# InverterConnector.net
KiCad netlist of a schematic drawn in Altium Designer
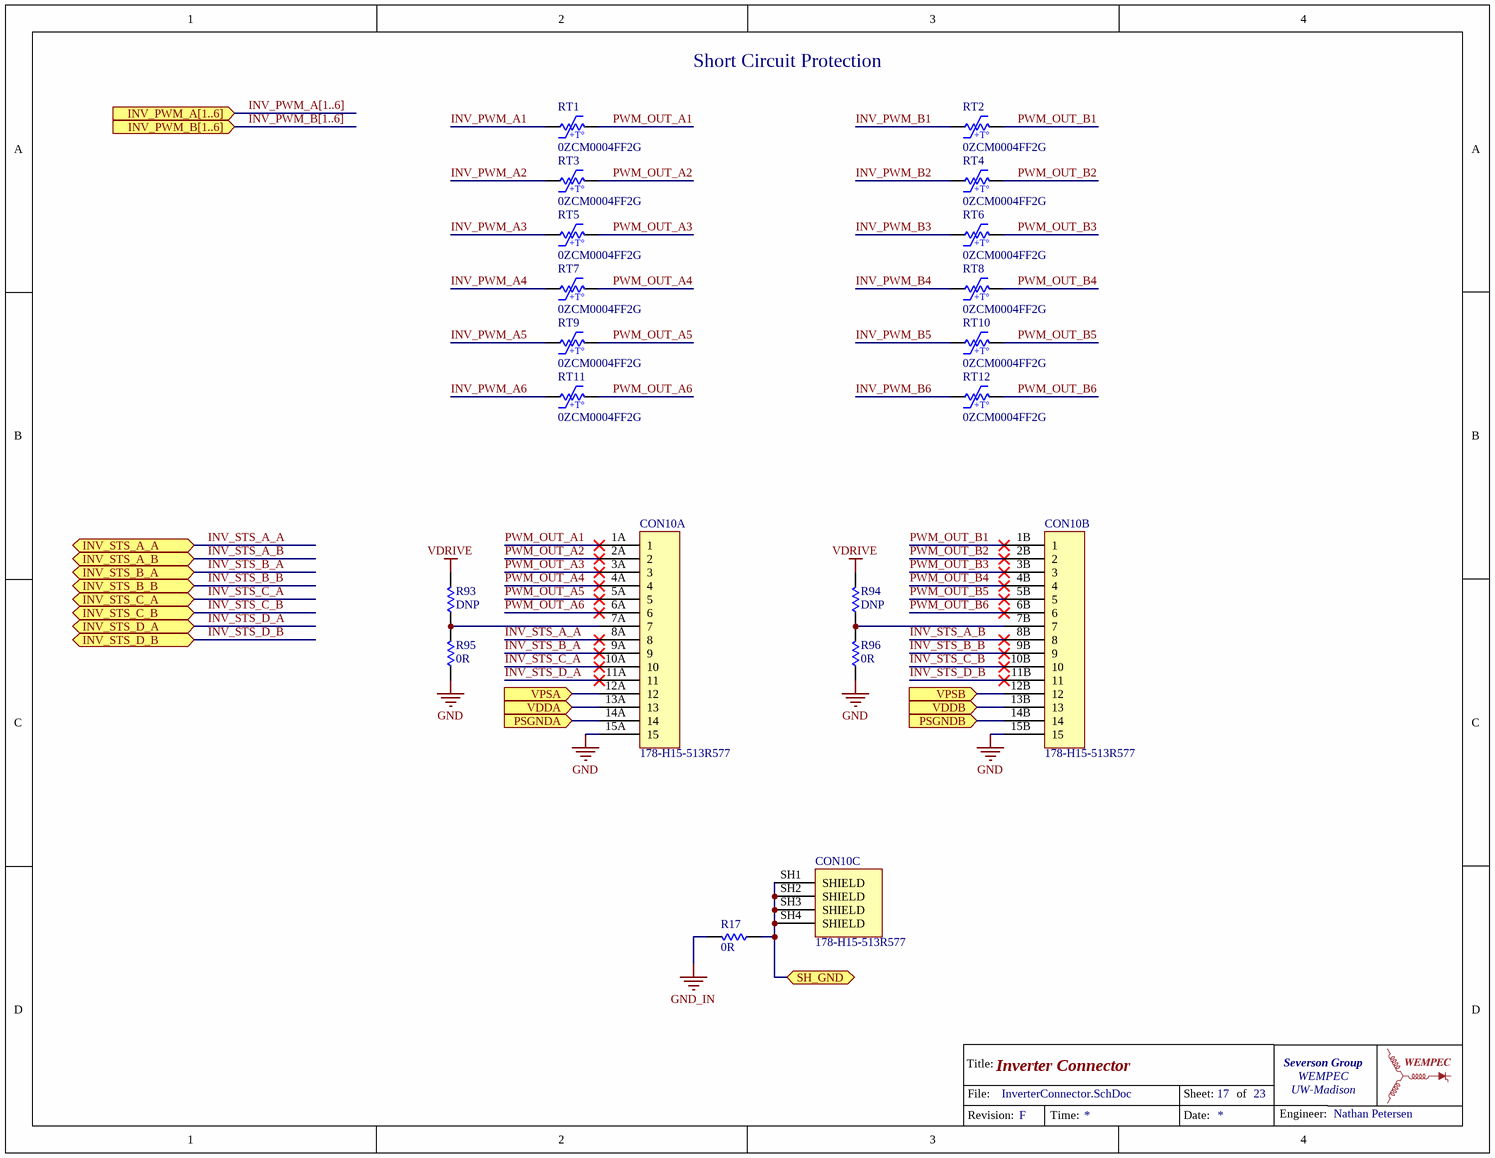
[diagram p0: InverterConnector.SchDoc]

(export (version "E")
  (design (tool "Eeschema 10.0.6"))
  (components
    (comp (ref "CON10")
      (value "178-H15-513R577")
      (footprint "178-H15-513R577")
      (description "CONN D-SUB PLUG 15POS R/A SLDR")
      (libsource (lib "AMDC") (part "178-H15-513R577"))
    )
    (comp (ref "R17")
      (value "0R")
      (footprint "1206-RES")
      (description "Resistor")
      (libsource (lib "AMDC") (part "Resistor"))
    )
    (comp (ref "R93")
      (value "DNP")
      (footprint "1206-RES")
      (description "Resistor")
      (libsource (lib "AMDC") (part "Resistor"))
    )
    (comp (ref "R94")
      (value "DNP")
      (footprint "1206-RES")
      (description "Resistor")
      (libsource (lib "AMDC") (part "Resistor"))
    )
    (comp (ref "R95")
      (value "0R")
      (footprint "1206-RES")
      (description "Resistor")
      (libsource (lib "AMDC") (part "Resistor"))
    )
    (comp (ref "R96")
      (value "0R")
      (footprint "1206-RES")
      (description "Resistor")
      (libsource (lib "AMDC") (part "Resistor"))
    )
    (comp (ref "RT1")
      (value "0ZCM0004FF2G")
      (footprint "PTCC1607X06N")
      (description "PTC RESET FUSE 24V 40MA 0603")
      (libsource (lib "AMDC") (part "0ZCM0004FF2G"))
    )
    (comp (ref "RT2")
      (value "0ZCM0004FF2G")
      (footprint "PTCC1607X06N")
      (description "PTC RESET FUSE 24V 40MA 0603")
      (libsource (lib "AMDC") (part "0ZCM0004FF2G"))
    )
    (comp (ref "RT3")
      (value "0ZCM0004FF2G")
      (footprint "PTCC1607X06N")
      (description "PTC RESET FUSE 24V 40MA 0603")
      (libsource (lib "AMDC") (part "0ZCM0004FF2G"))
    )
    (comp (ref "RT4")
      (value "0ZCM0004FF2G")
      (footprint "PTCC1607X06N")
      (description "PTC RESET FUSE 24V 40MA 0603")
      (libsource (lib "AMDC") (part "0ZCM0004FF2G"))
    )
    (comp (ref "RT5")
      (value "0ZCM0004FF2G")
      (footprint "PTCC1607X06N")
      (description "PTC RESET FUSE 24V 40MA 0603")
      (libsource (lib "AMDC") (part "0ZCM0004FF2G"))
    )
    (comp (ref "RT6")
      (value "0ZCM0004FF2G")
      (footprint "PTCC1607X06N")
      (description "PTC RESET FUSE 24V 40MA 0603")
      (libsource (lib "AMDC") (part "0ZCM0004FF2G"))
    )
    (comp (ref "RT7")
      (value "0ZCM0004FF2G")
      (footprint "PTCC1607X06N")
      (description "PTC RESET FUSE 24V 40MA 0603")
      (libsource (lib "AMDC") (part "0ZCM0004FF2G"))
    )
    (comp (ref "RT8")
      (value "0ZCM0004FF2G")
      (footprint "PTCC1607X06N")
      (description "PTC RESET FUSE 24V 40MA 0603")
      (libsource (lib "AMDC") (part "0ZCM0004FF2G"))
    )
    (comp (ref "RT9")
      (value "0ZCM0004FF2G")
      (footprint "PTCC1607X06N")
      (description "PTC RESET FUSE 24V 40MA 0603")
      (libsource (lib "AMDC") (part "0ZCM0004FF2G"))
    )
    (comp (ref "RT10")
      (value "0ZCM0004FF2G")
      (footprint "PTCC1607X06N")
      (description "PTC RESET FUSE 24V 40MA 0603")
      (libsource (lib "AMDC") (part "0ZCM0004FF2G"))
    )
    (comp (ref "RT11")
      (value "0ZCM0004FF2G")
      (footprint "PTCC1607X06N")
      (description "PTC RESET FUSE 24V 40MA 0603")
      (libsource (lib "AMDC") (part "0ZCM0004FF2G"))
    )
    (comp (ref "RT12")
      (value "0ZCM0004FF2G")
      (footprint "PTCC1607X06N")
      (description "PTC RESET FUSE 24V 40MA 0603")
      (libsource (lib "AMDC") (part "0ZCM0004FF2G"))
    )
  )
  (nets
    (net (code "1") (name "/INV_PWM_A1") (class "Default")
      (node (ref "RT1") (pin "1") (pinfunction "1_1") (pintype "passive"))
    )
    (net (code "2") (name "/INV_PWM_A2") (class "Default")
      (node (ref "RT3") (pin "1") (pinfunction "1_1") (pintype "passive"))
    )
    (net (code "3") (name "/INV_PWM_A3") (class "Default")
      (node (ref "RT5") (pin "1") (pinfunction "1_1") (pintype "passive"))
    )
    (net (code "4") (name "/INV_PWM_A4") (class "Default")
      (node (ref "RT7") (pin "1") (pinfunction "1_1") (pintype "passive"))
    )
    (net (code "5") (name "/INV_PWM_A5") (class "Default")
      (node (ref "RT9") (pin "1") (pinfunction "1_1") (pintype "passive"))
    )
    (net (code "6") (name "/INV_PWM_A6") (class "Default")
      (node (ref "RT11") (pin "1") (pinfunction "1_1") (pintype "passive"))
    )
    (net (code "8") (name "/INV_PWM_B1") (class "Default")
      (node (ref "RT2") (pin "1") (pinfunction "1_1") (pintype "passive"))
    )
    (net (code "9") (name "/INV_PWM_B2") (class "Default")
      (node (ref "RT4") (pin "1") (pinfunction "1_1") (pintype "passive"))
    )
    (net (code "10") (name "/INV_PWM_B3") (class "Default")
      (node (ref "RT6") (pin "1") (pinfunction "1_1") (pintype "passive"))
    )
    (net (code "11") (name "/INV_PWM_B4") (class "Default")
      (node (ref "RT8") (pin "1") (pinfunction "1_1") (pintype "passive"))
    )
    (net (code "12") (name "/INV_PWM_B5") (class "Default")
      (node (ref "RT10") (pin "1") (pinfunction "1_1") (pintype "passive"))
    )
    (net (code "13") (name "/INV_PWM_B6") (class "Default")
      (node (ref "RT12") (pin "1") (pinfunction "1_1") (pintype "passive"))
    )
    (net (code "15") (name "/INV_STS_A_A") (class "Default")
      (node (ref "CON10") (pin "8A") (pinfunction "8_8A") (pintype "passive+no_connect"))
    )
    (net (code "16") (name "/INV_STS_A_B") (class "Default")
      (node (ref "CON10") (pin "8B") (pinfunction "8_8B") (pintype "passive+no_connect"))
    )
    (net (code "17") (name "/INV_STS_B_A") (class "Default")
      (node (ref "CON10") (pin "9A") (pinfunction "9_9A") (pintype "passive+no_connect"))
    )
    (net (code "18") (name "/INV_STS_B_B") (class "Default")
      (node (ref "CON10") (pin "9B") (pinfunction "9_9B") (pintype "passive+no_connect"))
    )
    (net (code "19") (name "/INV_STS_C_A") (class "Default")
      (node (ref "CON10") (pin "10A") (pinfunction "10_10A") (pintype "passive+no_connect"))
    )
    (net (code "20") (name "/INV_STS_C_B") (class "Default")
      (node (ref "CON10") (pin "10B") (pinfunction "10_10B") (pintype "passive+no_connect"))
    )
    (net (code "21") (name "/INV_STS_D_A") (class "Default")
      (node (ref "CON10") (pin "11A") (pinfunction "11_11A") (pintype "passive+no_connect"))
    )
    (net (code "22") (name "/INV_STS_D_B") (class "Default")
      (node (ref "CON10") (pin "11B") (pinfunction "11_11B") (pintype "passive+no_connect"))
    )
    (net (code "23") (name "/PSGNDA") (class "Default")
      (node (ref "CON10") (pin "14A") (pinfunction "14_14A") (pintype "passive"))
    )
    (net (code "24") (name "/PSGNDB") (class "Default")
      (node (ref "CON10") (pin "14B") (pinfunction "14_14B") (pintype "passive"))
    )
    (net (code "25") (name "/PWM_OUT_A1") (class "Default")
      (node (ref "CON10") (pin "1A") (pinfunction "1_1A") (pintype "passive"))
      (node (ref "RT1") (pin "2") (pinfunction "2_2") (pintype "passive"))
    )
    (net (code "26") (name "/PWM_OUT_A2") (class "Default")
      (node (ref "CON10") (pin "2A") (pinfunction "2_2A") (pintype "passive"))
      (node (ref "RT3") (pin "2") (pinfunction "2_2") (pintype "passive"))
    )
    (net (code "27") (name "/PWM_OUT_A3") (class "Default")
      (node (ref "CON10") (pin "3A") (pinfunction "3_3A") (pintype "passive"))
      (node (ref "RT5") (pin "2") (pinfunction "2_2") (pintype "passive"))
    )
    (net (code "28") (name "/PWM_OUT_A4") (class "Default")
      (node (ref "CON10") (pin "4A") (pinfunction "4_4A") (pintype "passive"))
      (node (ref "RT7") (pin "2") (pinfunction "2_2") (pintype "passive"))
    )
    (net (code "29") (name "/PWM_OUT_A5") (class "Default")
      (node (ref "CON10") (pin "5A") (pinfunction "5_5A") (pintype "passive"))
      (node (ref "RT9") (pin "2") (pinfunction "2_2") (pintype "passive"))
    )
    (net (code "30") (name "/PWM_OUT_A6") (class "Default")
      (node (ref "CON10") (pin "6A") (pinfunction "6_6A") (pintype "passive"))
      (node (ref "RT11") (pin "2") (pinfunction "2_2") (pintype "passive"))
    )
    (net (code "31") (name "/PWM_OUT_B1") (class "Default")
      (node (ref "CON10") (pin "1B") (pinfunction "1_1B") (pintype "passive"))
      (node (ref "RT2") (pin "2") (pinfunction "2_2") (pintype "passive"))
    )
    (net (code "32") (name "/PWM_OUT_B2") (class "Default")
      (node (ref "CON10") (pin "2B") (pinfunction "2_2B") (pintype "passive"))
      (node (ref "RT4") (pin "2") (pinfunction "2_2") (pintype "passive"))
    )
    (net (code "33") (name "/PWM_OUT_B3") (class "Default")
      (node (ref "CON10") (pin "3B") (pinfunction "3_3B") (pintype "passive"))
      (node (ref "RT6") (pin "2") (pinfunction "2_2") (pintype "passive"))
    )
    (net (code "34") (name "/PWM_OUT_B4") (class "Default")
      (node (ref "CON10") (pin "4B") (pinfunction "4_4B") (pintype "passive"))
      (node (ref "RT8") (pin "2") (pinfunction "2_2") (pintype "passive"))
    )
    (net (code "35") (name "/PWM_OUT_B5") (class "Default")
      (node (ref "CON10") (pin "5B") (pinfunction "5_5B") (pintype "passive"))
      (node (ref "RT10") (pin "2") (pinfunction "2_2") (pintype "passive"))
    )
    (net (code "36") (name "/PWM_OUT_B6") (class "Default")
      (node (ref "CON10") (pin "6B") (pinfunction "6_6B") (pintype "passive"))
      (node (ref "RT12") (pin "2") (pinfunction "2_2") (pintype "passive"))
    )
    (net (code "37") (name "/SH_GND") (class "Default")
      (node (ref "CON10") (pin "SH1") (pinfunction "SHIELD_SH1") (pintype "passive"))
      (node (ref "CON10") (pin "SH2") (pinfunction "SHIELD_SH2") (pintype "passive"))
      (node (ref "CON10") (pin "SH3") (pinfunction "SHIELD_SH3") (pintype "passive"))
      (node (ref "CON10") (pin "SH4") (pinfunction "SHIELD_SH4") (pintype "passive"))
      (node (ref "R17") (pin "1") (pinfunction "1_1") (pintype "passive"))
    )
    (net (code "38") (name "/VDDA") (class "Default")
      (node (ref "CON10") (pin "13A") (pinfunction "13_13A") (pintype "passive"))
    )
    (net (code "39") (name "/VDDB") (class "Default")
      (node (ref "CON10") (pin "13B") (pinfunction "13_13B") (pintype "passive"))
    )
    (net (code "40") (name "/VPSA") (class "Default")
      (node (ref "CON10") (pin "12A") (pinfunction "12_12A") (pintype "passive"))
    )
    (net (code "41") (name "/VPSB") (class "Default")
      (node (ref "CON10") (pin "12B") (pinfunction "12_12B") (pintype "passive"))
    )
    (net (code "42") (name "GND") (class "Default")
      (node (ref "CON10") (pin "15A") (pinfunction "15_15A") (pintype "passive"))
      (node (ref "CON10") (pin "15B") (pinfunction "15_15B") (pintype "passive"))
      (node (ref "R95") (pin "1") (pinfunction "1_1") (pintype "passive"))
      (node (ref "R96") (pin "1") (pinfunction "1_1") (pintype "passive"))
    )
    (net (code "43") (name "GND_IN") (class "Default")
      (node (ref "R17") (pin "2") (pinfunction "2_2") (pintype "passive"))
    )
    (net (code "44") (name "Net-(CON10A-7)") (class "Default")
      (node (ref "CON10") (pin "7A") (pinfunction "7_7A") (pintype "passive"))
      (node (ref "R93") (pin "1") (pinfunction "1_1") (pintype "passive"))
      (node (ref "R95") (pin "2") (pinfunction "2_2") (pintype "passive"))
    )
    (net (code "45") (name "Net-(CON10B-7)") (class "Default")
      (node (ref "CON10") (pin "7B") (pinfunction "7_7B") (pintype "passive"))
      (node (ref "R94") (pin "1") (pinfunction "1_1") (pintype "passive"))
      (node (ref "R96") (pin "2") (pinfunction "2_2") (pintype "passive"))
    )
    (net (code "46") (name "VDRIVE") (class "Default")
      (node (ref "R93") (pin "2") (pinfunction "2_2") (pintype "passive"))
      (node (ref "R94") (pin "2") (pinfunction "2_2") (pintype "passive"))
    )
  )
)
